# io_headers.net
KiCad netlist of a schematic drawn in Altium Designer
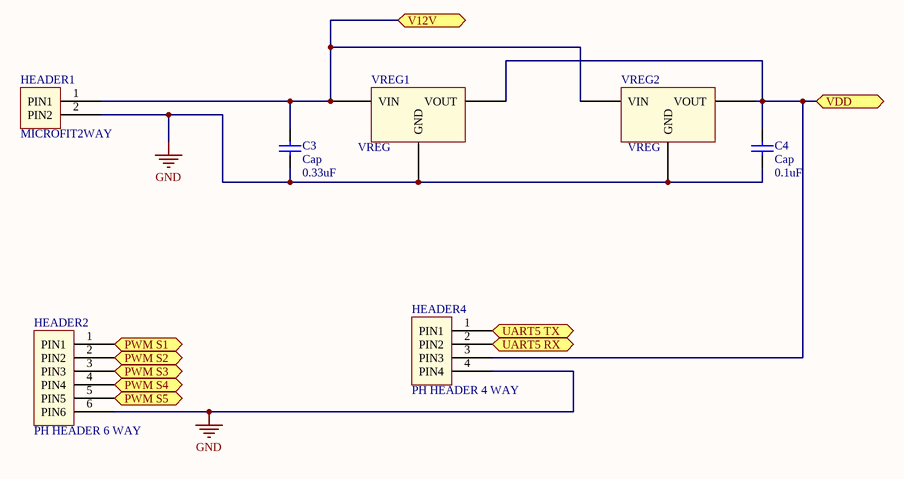
[diagram p0: io_headers.SchDoc]

(export (version "E")
  (design (tool "Eeschema 10.0.6"))
  (components
    (comp (ref "C3")
      (value "Cap")
      (footprint "RAD-0.3")
      (description "Capacitor")
      (fields (field (name "ALTIUM_VALUE") "0.33uF") (field (name "PUBLISHER") "Altium Limited"))
      (libsource (lib "Miscellaneous Devices") (part "Cap"))
    )
    (comp (ref "C4")
      (value "Cap")
      (footprint "RAD-0.3")
      (description "Capacitor")
      (fields (field (name "ALTIUM_VALUE") "0.1uF") (field (name "PUBLISHER") "Altium Limited"))
      (libsource (lib "Miscellaneous Devices") (part "Cap"))
    )
    (comp (ref "HEADER1")
      (value "MICROFIT2WAY")
      (footprint "MICROFIT2WAY")
      (description "MICROFIT2WAY HEADER")
      (libsource (lib "MICROFIT_2WAY") (part "MICROFIT2WAY HEADER"))
    )
    (comp (ref "HEADER2")
      (value "PH HEADER 6 WAY")
      (footprint "PH CONNECTOR 6 WAY")
      (libsource (lib "PH_HEADER_6_WAY") (part "PH HEADER 6 WAY"))
    )
    (comp (ref "HEADER4")
      (value "PH HEADER 4 WAY")
      (footprint "PH_HEADER 4WAY")
      (libsource (lib "PH_HEADER_4_WAY") (part "PH HEADER 4 WAY"))
    )
    (comp (ref "VREG1")
      (value "VREG")
      (footprint "TO-220 VREG")
      (description "VOLTAGE REGULATOR")
      (libsource (lib "VREG") (part "VOLTAGE REGULATOR"))
    )
    (comp (ref "VREG2")
      (value "VREG")
      (footprint "TO-220 VREG")
      (description "VOLTAGE REGULATOR")
      (libsource (lib "VREG") (part "VOLTAGE REGULATOR"))
    )
  )
  (nets
    (net (code "1") (name "/PWM S1") (class "Default")
      (node (ref "HEADER2") (pin "1") (pinfunction "PIN1_1") (pintype "passive"))
    )
    (net (code "2") (name "/PWM S2") (class "Default")
      (node (ref "HEADER2") (pin "2") (pinfunction "PIN2_2") (pintype "passive"))
    )
    (net (code "3") (name "/PWM S3") (class "Default")
      (node (ref "HEADER2") (pin "3") (pinfunction "PIN3_3") (pintype "passive"))
    )
    (net (code "4") (name "/PWM S4") (class "Default")
      (node (ref "HEADER2") (pin "4") (pinfunction "PIN4_4") (pintype "passive"))
    )
    (net (code "5") (name "/PWM S5") (class "Default")
      (node (ref "HEADER2") (pin "5") (pinfunction "PIN5_5") (pintype "passive"))
    )
    (net (code "6") (name "/UART5 RX") (class "Default")
      (node (ref "HEADER4") (pin "2") (pinfunction "PIN2_2") (pintype "passive"))
    )
    (net (code "7") (name "/UART5 TX") (class "Default")
      (node (ref "HEADER4") (pin "1") (pinfunction "PIN1_1") (pintype "passive"))
    )
    (net (code "8") (name "/V12V") (class "Default")
      (node (ref "C3") (pin "2") (pinfunction "2_2") (pintype "passive"))
      (node (ref "HEADER1") (pin "1") (pinfunction "PIN1_1") (pintype "passive"))
      (node (ref "VREG1") (pin "1") (pinfunction "VIN_1") (pintype "passive"))
      (node (ref "VREG2") (pin "1") (pinfunction "VIN_1") (pintype "passive"))
    )
    (net (code "9") (name "/VDD") (class "Default")
      (node (ref "C4") (pin "2") (pinfunction "2_2") (pintype "passive"))
      (node (ref "HEADER4") (pin "3") (pinfunction "PIN3_3") (pintype "passive"))
      (node (ref "VREG1") (pin "3") (pinfunction "VOUT_3") (pintype "passive"))
      (node (ref "VREG2") (pin "3") (pinfunction "VOUT_3") (pintype "passive"))
    )
    (net (code "10") (name "GND") (class "Default")
      (node (ref "C3") (pin "1") (pinfunction "1_1") (pintype "passive"))
      (node (ref "C4") (pin "1") (pinfunction "1_1") (pintype "passive"))
      (node (ref "HEADER1") (pin "2") (pinfunction "PIN2_2") (pintype "passive"))
      (node (ref "HEADER2") (pin "6") (pinfunction "PIN6_6") (pintype "passive"))
      (node (ref "HEADER4") (pin "4") (pinfunction "PIN4_4") (pintype "passive"))
      (node (ref "VREG1") (pin "2") (pinfunction "GND_2") (pintype "passive"))
      (node (ref "VREG2") (pin "2") (pinfunction "GND_2") (pintype "passive"))
    )
  )
)
